# usb_keyboard.net
KiCad netlist of a schematic drawn in EAGLE
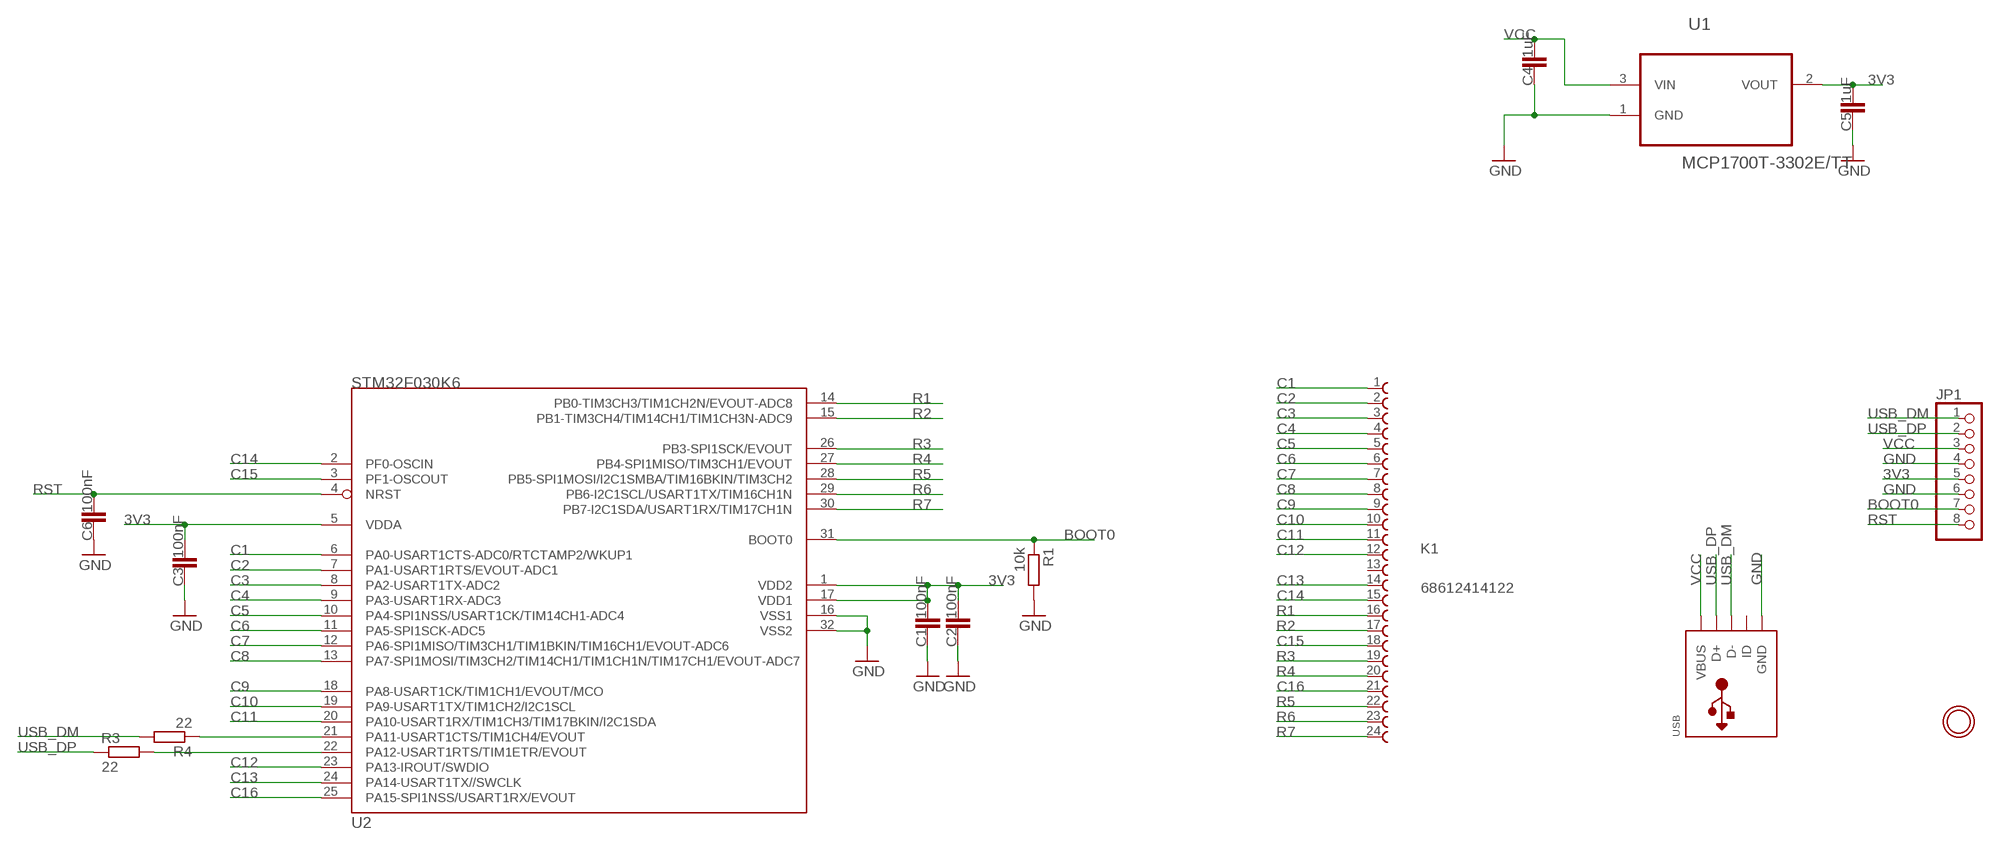
[diagram p0: schematic, sheet 1]

(export (version "E")
  (design (tool "Eeschema 10.0.6"))
  (components
    (comp (ref "C1")
      (value "100nF")
      (footprint "eagle-import:C0603K")
      (libsource (lib "eagle-import") (part "C-EUC0603K"))
    )
    (comp (ref "C2")
      (value "100nF")
      (footprint "eagle-import:C0603K")
      (libsource (lib "eagle-import") (part "C-EUC0603K"))
    )
    (comp (ref "C3")
      (value "100nF")
      (footprint "eagle-import:C0603K")
      (libsource (lib "eagle-import") (part "C-EUC0603K"))
    )
    (comp (ref "C4")
      (value "1uF")
      (footprint "eagle-import:C0603K")
      (libsource (lib "eagle-import") (part "C-EUC0603K"))
    )
    (comp (ref "C5")
      (value "1uF")
      (footprint "eagle-import:C0603K")
      (libsource (lib "eagle-import") (part "C-EUC0603K"))
    )
    (comp (ref "C6")
      (value "100nF")
      (footprint "eagle-import:C0603K")
      (libsource (lib "eagle-import") (part "C-EUC0603K"))
    )
    (comp (ref "JP1")
      (value "HEADER-1X8ROUND")
      (footprint "eagle-import:1X08_ROUND")
      (libsource (lib "eagle-import") (part "HEADER-1X8ROUND"))
    )
    (comp (ref "K1")
      (value "68612414122")
      (footprint "eagle-import:68612414122")
      (libsource (lib "eagle-import") (part "68612414122"))
    )
    (comp (ref "R1")
      (value "10k")
      (footprint "eagle-import:R0603")
      (libsource (lib "eagle-import") (part "R-EU_R0603"))
    )
    (comp (ref "R3")
      (value "22")
      (footprint "eagle-import:R0603")
      (libsource (lib "eagle-import") (part "R-EU_R0603"))
    )
    (comp (ref "R4")
      (value "22")
      (footprint "eagle-import:R0603")
      (libsource (lib "eagle-import") (part "R-EU_R0603"))
    )
    (comp (ref "U$2")
      (value "MOUNTINGHOLE2.0")
      (footprint "eagle-import:MOUNTINGHOLE_2.0_PLATED")
      (libsource (lib "eagle-import") (part "MOUNTINGHOLE2.0"))
    )
    (comp (ref "U1")
      (value "MCP1700T-3302E/TT")
      (footprint "eagle-import:SOT95P237X112-3N")
      (libsource (lib "eagle-import") (part "MCP1700T-3302E/TT"))
    )
    (comp (ref "U2")
      (value "STM32F030K6")
      (footprint "eagle-import:LQFP32")
      (libsource (lib "eagle-import") (part "STM32F030K6"))
    )
    (comp (ref "USB")
      (value "USBMOLEX")
      (footprint "eagle-import:USB-MINIB-THM-MOLEX")
      (libsource (lib "eagle-import") (part "USBMOLEX"))
    )
  )
  (nets
    (net (code "1") (name "/3V3") (class "Default")
      (node (ref "C1") (pin "2") (pinfunction "2_2") (pintype "passive"))
      (node (ref "C2") (pin "2") (pinfunction "2_2") (pintype "passive"))
      (node (ref "C3") (pin "2") (pinfunction "2_2") (pintype "passive"))
      (node (ref "C5") (pin "2") (pinfunction "2_2") (pintype "passive"))
      (node (ref "JP1") (pin "5") (pinfunction "5_5") (pintype "passive"))
      (node (ref "U1") (pin "2") (pinfunction "VOUT_2") (pintype "output"))
      (node (ref "U2") (pin "1") (pinfunction "VDD2_1") (pintype "bidirectional"))
      (node (ref "U2") (pin "17") (pinfunction "VDD1_17") (pintype "bidirectional"))
      (node (ref "U2") (pin "5") (pinfunction "VDDA_5") (pintype "bidirectional"))
    )
    (net (code "2") (name "/BOOT0") (class "Default")
      (node (ref "JP1") (pin "7") (pinfunction "7_7") (pintype "passive"))
      (node (ref "R1") (pin "1") (pinfunction "1_1") (pintype "passive"))
      (node (ref "U2") (pin "31") (pinfunction "BOOT0_31") (pintype "input"))
    )
    (net (code "3") (name "/C1") (class "Default")
      (node (ref "K1") (pin "1") (pinfunction "1_1") (pintype "passive"))
      (node (ref "U2") (pin "6") (pinfunction "PA0-USART1CTS-ADC0/RTCTAMP2/WKUP1_6") (pintype "bidirectional"))
    )
    (net (code "4") (name "/C2") (class "Default")
      (node (ref "K1") (pin "2") (pinfunction "2_2") (pintype "passive"))
      (node (ref "U2") (pin "7") (pinfunction "PA1-USART1RTS/EVOUT-ADC1_7") (pintype "bidirectional"))
    )
    (net (code "5") (name "/C3") (class "Default")
      (node (ref "K1") (pin "3") (pinfunction "3_3") (pintype "passive"))
      (node (ref "U2") (pin "8") (pinfunction "PA2-USART1TX-ADC2_8") (pintype "bidirectional"))
    )
    (net (code "6") (name "/C4") (class "Default")
      (node (ref "K1") (pin "4") (pinfunction "4_4") (pintype "passive"))
      (node (ref "U2") (pin "9") (pinfunction "PA3-USART1RX-ADC3_9") (pintype "bidirectional"))
    )
    (net (code "7") (name "/C5") (class "Default")
      (node (ref "K1") (pin "5") (pinfunction "5_5") (pintype "passive"))
      (node (ref "U2") (pin "10") (pinfunction "PA4-SPI1NSS/USART1CK/TIM14CH1-ADC4_10") (pintype "bidirectional"))
    )
    (net (code "8") (name "/C6") (class "Default")
      (node (ref "K1") (pin "6") (pinfunction "6_6") (pintype "passive"))
      (node (ref "U2") (pin "11") (pinfunction "PA5-SPI1SCK-ADC5_11") (pintype "bidirectional"))
    )
    (net (code "9") (name "/C7") (class "Default")
      (node (ref "K1") (pin "7") (pinfunction "7_7") (pintype "passive"))
      (node (ref "U2") (pin "12") (pinfunction "PA6-SPI1MISO/TIM3CH1/TIM1BKIN/TIM16CH1/EVOUT-ADC6_12") (pintype "bidirectional"))
    )
    (net (code "10") (name "/C8") (class "Default")
      (node (ref "K1") (pin "8") (pinfunction "8_8") (pintype "passive"))
      (node (ref "U2") (pin "13") (pinfunction "PA7-SPI1MOSI/TIM3CH2/TIM14CH1/TIM1CH1N/TIM17CH1/EVOUT-ADC7_13") (pintype "bidirectional"))
    )
    (net (code "11") (name "/C9") (class "Default")
      (node (ref "K1") (pin "9") (pinfunction "9_9") (pintype "passive"))
      (node (ref "U2") (pin "18") (pinfunction "PA8-USART1CK/TIM1CH1/EVOUT/MCO_18") (pintype "bidirectional"))
    )
    (net (code "12") (name "/C10") (class "Default")
      (node (ref "K1") (pin "10") (pinfunction "10_10") (pintype "passive"))
      (node (ref "U2") (pin "19") (pinfunction "PA9-USART1TX/TIM1CH2/I2C1SCL_19") (pintype "bidirectional"))
    )
    (net (code "13") (name "/C11") (class "Default")
      (node (ref "K1") (pin "11") (pinfunction "11_11") (pintype "passive"))
      (node (ref "U2") (pin "20") (pinfunction "PA10-USART1RX/TIM1CH3/TIM17BKIN/I2C1SDA_20") (pintype "bidirectional"))
    )
    (net (code "14") (name "/C12") (class "Default")
      (node (ref "K1") (pin "12") (pinfunction "12_12") (pintype "passive"))
      (node (ref "U2") (pin "23") (pinfunction "PA13-IROUT/SWDIO_23") (pintype "bidirectional"))
    )
    (net (code "15") (name "/C13") (class "Default")
      (node (ref "K1") (pin "14") (pinfunction "14_14") (pintype "passive"))
      (node (ref "U2") (pin "24") (pinfunction "PA14-USART1TX//SWCLK_24") (pintype "bidirectional"))
    )
    (net (code "16") (name "/C14") (class "Default")
      (node (ref "K1") (pin "15") (pinfunction "15_15") (pintype "passive"))
      (node (ref "U2") (pin "2") (pinfunction "PF0-OSCIN_2") (pintype "bidirectional"))
    )
    (net (code "17") (name "/C15") (class "Default")
      (node (ref "K1") (pin "18") (pinfunction "18_18") (pintype "passive"))
      (node (ref "U2") (pin "3") (pinfunction "PF1-OSCOUT_3") (pintype "bidirectional"))
    )
    (net (code "18") (name "/C16") (class "Default")
      (node (ref "K1") (pin "21") (pinfunction "21_21") (pintype "passive"))
      (node (ref "U2") (pin "25") (pinfunction "PA15-SPI1NSS/USART1RX/EVOUT_25") (pintype "bidirectional"))
    )
    (net (code "19") (name "/R1") (class "Default")
      (node (ref "K1") (pin "16") (pinfunction "16_16") (pintype "passive"))
      (node (ref "U2") (pin "14") (pinfunction "PB0-TIM3CH3/TIM1CH2N/EVOUT-ADC8_14") (pintype "bidirectional"))
    )
    (net (code "20") (name "/R2") (class "Default")
      (node (ref "K1") (pin "17") (pinfunction "17_17") (pintype "passive"))
      (node (ref "U2") (pin "15") (pinfunction "PB1-TIM3CH4/TIM14CH1/TIM1CH3N-ADC9_15") (pintype "bidirectional"))
    )
    (net (code "21") (name "/R3") (class "Default")
      (node (ref "K1") (pin "19") (pinfunction "19_19") (pintype "passive"))
      (node (ref "U2") (pin "26") (pinfunction "PB3-SPI1SCK/EVOUT_26") (pintype "bidirectional"))
    )
    (net (code "22") (name "/R4") (class "Default")
      (node (ref "K1") (pin "20") (pinfunction "20_20") (pintype "passive"))
      (node (ref "U2") (pin "27") (pinfunction "PB4-SPI1MISO/TIM3CH1/EVOUT_27") (pintype "bidirectional"))
    )
    (net (code "23") (name "/R5") (class "Default")
      (node (ref "K1") (pin "22") (pinfunction "22_22") (pintype "passive"))
      (node (ref "U2") (pin "28") (pinfunction "PB5-SPI1MOSI/I2C1SMBA/TIM16BKIN/TIM3CH2_28") (pintype "bidirectional"))
    )
    (net (code "24") (name "/R6") (class "Default")
      (node (ref "K1") (pin "23") (pinfunction "23_23") (pintype "passive"))
      (node (ref "U2") (pin "29") (pinfunction "PB6-I2C1SCL/USART1TX/TIM16CH1N_29") (pintype "bidirectional"))
    )
    (net (code "25") (name "/R7") (class "Default")
      (node (ref "K1") (pin "24") (pinfunction "24_24") (pintype "passive"))
      (node (ref "U2") (pin "30") (pinfunction "PB7-I2C1SDA/USART1RX/TIM17CH1N_30") (pintype "bidirectional"))
    )
    (net (code "26") (name "/RST") (class "Default")
      (node (ref "C6") (pin "2") (pinfunction "2_2") (pintype "passive"))
      (node (ref "JP1") (pin "8") (pinfunction "8_8") (pintype "passive"))
      (node (ref "U2") (pin "4") (pinfunction "NRST_4") (pintype "bidirectional"))
    )
    (net (code "27") (name "/USB_DM") (class "Default")
      (node (ref "JP1") (pin "1") (pinfunction "1_1") (pintype "passive"))
      (node (ref "R4") (pin "2") (pinfunction "2_2") (pintype "passive"))
      (node (ref "USB") (pin "D-") (pinfunction "D-_D-") (pintype "bidirectional"))
    )
    (net (code "28") (name "/USB_DP") (class "Default")
      (node (ref "JP1") (pin "2") (pinfunction "2_2") (pintype "passive"))
      (node (ref "R3") (pin "1") (pinfunction "1_1") (pintype "passive"))
      (node (ref "USB") (pin "D+") (pinfunction "D+_D+") (pintype "bidirectional"))
    )
    (net (code "29") (name "/VCC") (class "Default")
      (node (ref "C4") (pin "2") (pinfunction "2_2") (pintype "passive"))
      (node (ref "JP1") (pin "3") (pinfunction "3_3") (pintype "passive"))
      (node (ref "U1") (pin "3") (pinfunction "VIN_3") (pintype "input"))
      (node (ref "USB") (pin "VBUS") (pinfunction "VBUS_VBUS") (pintype "power_in"))
    )
    (net (code "30") (name "GND") (class "Default")
      (node (ref "C1") (pin "1") (pinfunction "1_1") (pintype "passive"))
      (node (ref "C2") (pin "1") (pinfunction "1_1") (pintype "passive"))
      (node (ref "C3") (pin "1") (pinfunction "1_1") (pintype "passive"))
      (node (ref "C4") (pin "1") (pinfunction "1_1") (pintype "passive"))
      (node (ref "C5") (pin "1") (pinfunction "1_1") (pintype "passive"))
      (node (ref "C6") (pin "1") (pinfunction "1_1") (pintype "passive"))
      (node (ref "JP1") (pin "4") (pinfunction "4_4") (pintype "passive"))
      (node (ref "JP1") (pin "6") (pinfunction "6_6") (pintype "passive"))
      (node (ref "R1") (pin "2") (pinfunction "2_2") (pintype "passive"))
      (node (ref "U1") (pin "1") (pinfunction "GND_1") (pintype "passive"))
      (node (ref "U2") (pin "16") (pinfunction "VSS1_16") (pintype "bidirectional"))
      (node (ref "U2") (pin "32") (pinfunction "VSS2_32") (pintype "bidirectional"))
      (node (ref "USB") (pin "GND") (pinfunction "GND_GND") (pintype "power_in"))
    )
    (net (code "31") (name "Net-(U2-PA11-USART1CTS{slash}TIM1CH4{slash}EVOUT)") (class "Default")
      (node (ref "R4") (pin "1") (pinfunction "1_1") (pintype "passive"))
      (node (ref "U2") (pin "21") (pinfunction "PA11-USART1CTS/TIM1CH4/EVOUT_21") (pintype "bidirectional"))
    )
    (net (code "32") (name "Net-(U2-PA12-USART1RTS{slash}TIM1ETR{slash}EVOUT)") (class "Default")
      (node (ref "R3") (pin "2") (pinfunction "2_2") (pintype "passive"))
      (node (ref "U2") (pin "22") (pinfunction "PA12-USART1RTS/TIM1ETR/EVOUT_22") (pintype "bidirectional"))
    )
    (net (code "33") (name "unconnected-(K1-Pad13)") (class "Default")
      (node (ref "K1") (pin "13") (pinfunction "13_13") (pintype "passive"))
    )
    (net (code "34") (name "unconnected-(USB-PadID)") (class "Default")
      (node (ref "USB") (pin "ID") (pinfunction "ID_ID") (pintype "bidirectional"))
    )
  )
)
